# milliohm-adapter.net
KiCad netlist of a schematic drawn in Altium Designer
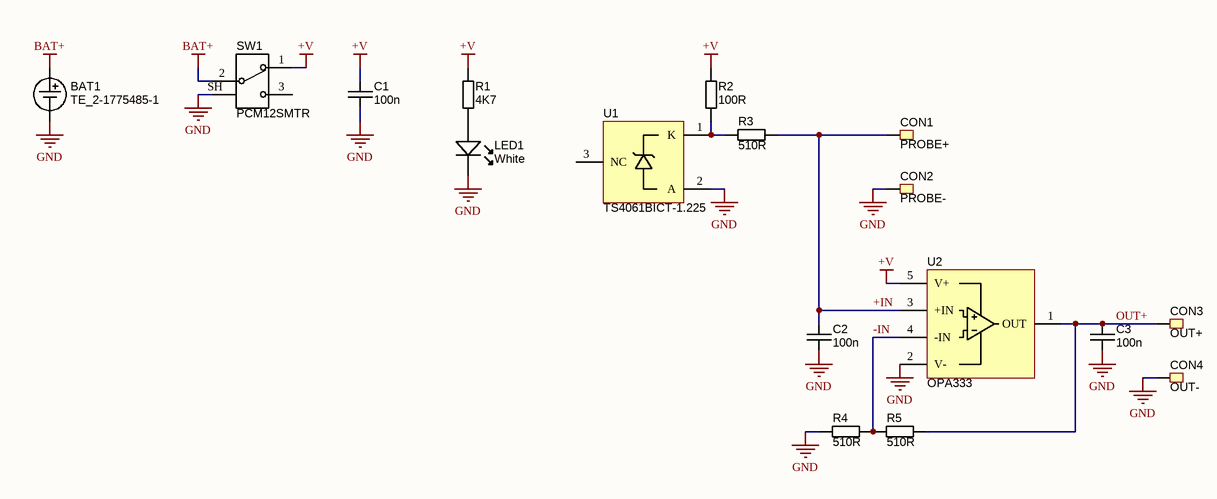
[diagram p0: milliohm-adapter.SchDoc]

(export (version "E")
  (design (tool "Eeschema 10.0.6"))
  (components
    (comp (ref "BAT1")
      (value "TE_2-1775485-1")
      (footprint "TE_2-1775485-1")
      (libsource (lib "milliohm-adapter") (part "TE_2-1775485-1"))
    )
    (comp (ref "C1")
      (value "100n")
      (footprint "CAPC1608X90N")
      (description "Capacitor SMD Cer 100nF 10% 50V X7R 0603")
      (fields (field (name "TOLERANCE") "±10%") (field (name "Comment") "approved sub OK"))
      (libsource (lib "PBL - Capacitors") (part "CAPC_100n_0603_X7R_50V_10%"))
    )
    (comp (ref "C2")
      (value "100n")
      (footprint "CAPC1608X90N")
      (description "Capacitor SMD Cer 100nF 10% 50V X7R 0603")
      (fields (field (name "TOLERANCE") "±10%") (field (name "Comment") "approved sub OK"))
      (libsource (lib "PBL - Capacitors") (part "CAPC_100n_0603_X7R_50V_10%"))
    )
    (comp (ref "C3")
      (value "100n")
      (footprint "CAPC1608X90N")
      (description "Capacitor SMD Cer 100nF 10% 50V X7R 0603")
      (fields (field (name "TOLERANCE") "±10%") (field (name "Comment") "approved sub OK"))
      (libsource (lib "PBL - Capacitors") (part "CAPC_100n_0603_X7R_50V_10%"))
    )
    (comp (ref "CON1")
      (value "PROBE+")
      (footprint "AMASS-GC4010-F-THT")
      (libsource (lib "milliohm-adapter") (part "BULLET_4mm"))
    )
    (comp (ref "CON2")
      (value "PROBE-")
      (footprint "AMASS-GC4010-F-THT")
      (libsource (lib "milliohm-adapter") (part "BULLET_4mm"))
    )
    (comp (ref "CON3")
      (value "OUT+")
      (footprint "AMASS-GC4010-M-THT")
      (libsource (lib "milliohm-adapter") (part "BULLET_4mm"))
    )
    (comp (ref "CON4")
      (value "OUT-")
      (footprint "AMASS-GC4010-M-THT")
      (libsource (lib "milliohm-adapter") (part "BULLET_4mm"))
    )
    (comp (ref "LED1")
      (value "White")
      (footprint "LED-0603-WHITE")
      (description "LED 0603 SMD Bright White 8700K")
      (libsource (lib "PBL - Light Sources") (part "LED_SMD_White_0603_Bright"))
    )
    (comp (ref "R1")
      (value "4K7")
      (footprint "RESC1608X55N")
      (description "Resistor SMD chip 4.7k Ohm 0.1W 5% 0603")
      (fields (field (name "TOLERANCE") "±5%") (field (name "Comment") "Thick Film"))
      (libsource (lib "PBL - Resistors") (part "RES_4K7_0603_5%"))
    )
    (comp (ref "R2")
      (value "100R")
      (footprint "RESC1608X55N")
      (description "Resistor SMD chip 100 Ohm 0.1W 1% 0603")
      (fields (field (name "TOLERANCE") "±1%") (field (name "Comment") "Thick Film"))
      (libsource (lib "PBL - Resistors") (part "RES_100R_0603_1%"))
    )
    (comp (ref "R3")
      (value "510R")
      (footprint "RESC2012X70N")
      (description "Resistor SMD chip 510 Ohm 0.125W 1% 0805")
      (fields (field (name "TOLERANCE") "±1%") (field (name "Comment") "Thick Film"))
      (libsource (lib "PBL - Resistors") (part "RES_510R_0805_1%"))
    )
    (comp (ref "R4")
      (value "510R")
      (footprint "RESC2012X70N")
      (description "Resistor SMD chip 510 Ohm 0.125W 1% 0805")
      (fields (field (name "TOLERANCE") "±1%") (field (name "Comment") "Thick Film"))
      (libsource (lib "PBL - Resistors") (part "RES_510R_0805_1%"))
    )
    (comp (ref "R5")
      (value "510R")
      (footprint "RESC2012X70N")
      (description "Resistor SMD chip 510 Ohm 0.125W 1% 0805")
      (fields (field (name "TOLERANCE") "±1%") (field (name "Comment") "Thick Film"))
      (libsource (lib "PBL - Resistors") (part "RES_510R_0805_1%"))
    )
    (comp (ref "SW1")
      (value "PCM12SMTR")
      (footprint "PCM12SMTR")
      (libsource (lib "milliohm-adapter") (part "PCM12SMTR"))
    )
    (comp (ref "U1")
      (value "TS4061BICT-1.225")
      (footprint "TS4061_SOT323-3L")
      (libsource (lib "milliohm-adapter") (part "TS4061BICT-1.225"))
    )
    (comp (ref "U2")
      (value "OPA333")
      (footprint "TI_DBV0005A_SOT23-5")
      (libsource (lib "milliohm-adapter") (part "OPA333"))
    )
  )
  (nets
    (net (code "1") (name "+V") (class "Default")
      (node (ref "C1") (pin "1") (pintype "passive"))
      (node (ref "R1") (pin "1") (pinfunction "1_1") (pintype "passive"))
      (node (ref "R2") (pin "2") (pinfunction "2_2") (pintype "passive"))
      (node (ref "SW1") (pin "1") (pinfunction "1_1") (pintype "passive"))
      (node (ref "U2") (pin "5") (pinfunction "V+_5") (pintype "passive"))
    )
    (net (code "2") (name "/+IN") (class "Default")
      (node (ref "C2") (pin "1") (pintype "passive"))
      (node (ref "CON1") (pin "1") (pinfunction "1_1") (pintype "passive"))
      (node (ref "R3") (pin "1") (pinfunction "1_1") (pintype "passive"))
      (node (ref "U2") (pin "3") (pinfunction "+IN_3") (pintype "passive"))
    )
    (net (code "3") (name "/-IN") (class "Default")
      (node (ref "R4") (pin "1") (pinfunction "1_1") (pintype "passive"))
      (node (ref "R5") (pin "2") (pinfunction "2_2") (pintype "passive"))
      (node (ref "U2") (pin "4") (pinfunction "-IN_4") (pintype "passive"))
    )
    (net (code "4") (name "/OUT+") (class "Default")
      (node (ref "C3") (pin "1") (pintype "passive"))
      (node (ref "CON3") (pin "1") (pinfunction "1_1") (pintype "passive"))
      (node (ref "R5") (pin "1") (pinfunction "1_1") (pintype "passive"))
      (node (ref "U2") (pin "1") (pinfunction "OUT_1") (pintype "passive"))
    )
    (net (code "5") (name "BAT+") (class "Default")
      (node (ref "BAT1") (pin "plus") (pinfunction "plus_plus") (pintype "passive"))
      (node (ref "SW1") (pin "2") (pinfunction "2_2") (pintype "passive"))
    )
    (net (code "6") (name "GND") (class "Default")
      (node (ref "BAT1") (pin "minus") (pinfunction "minus_minus") (pintype "passive"))
      (node (ref "C1") (pin "2") (pintype "passive"))
      (node (ref "C2") (pin "2") (pintype "passive"))
      (node (ref "C3") (pin "2") (pintype "passive"))
      (node (ref "CON2") (pin "1") (pinfunction "1_1") (pintype "passive"))
      (node (ref "CON4") (pin "1") (pinfunction "1_1") (pintype "passive"))
      (node (ref "LED1") (pin "K") (pinfunction "K_K") (pintype "passive"))
      (node (ref "R4") (pin "2") (pinfunction "2_2") (pintype "passive"))
      (node (ref "SW1") (pin "SH") (pinfunction "SH_SH") (pintype "passive"))
      (node (ref "U1") (pin "2") (pinfunction "A_2") (pintype "passive"))
      (node (ref "U2") (pin "2") (pinfunction "V-_2") (pintype "passive"))
    )
    (net (code "7") (name "Net-(LED1-PadA)") (class "Default")
      (node (ref "LED1") (pin "A") (pinfunction "A_A") (pintype "passive"))
      (node (ref "R1") (pin "2") (pinfunction "2_2") (pintype "passive"))
    )
    (net (code "8") (name "Net-(U1-K)") (class "Default")
      (node (ref "R2") (pin "1") (pinfunction "1_1") (pintype "passive"))
      (node (ref "R3") (pin "2") (pinfunction "2_2") (pintype "passive"))
      (node (ref "U1") (pin "1") (pinfunction "K_1") (pintype "passive"))
    )
    (net (code "9") (name "unconnected-(SW1-Pad3)") (class "Default")
      (node (ref "SW1") (pin "3") (pinfunction "3_3") (pintype "passive"))
    )
    (net (code "10") (name "unconnected-(U1-NC-Pad3)") (class "Default")
      (node (ref "U1") (pin "3") (pinfunction "NC_3") (pintype "passive"))
    )
  )
)
